# LED_Weather_Display.net
KiCad netlist of a schematic drawn in EAGLE
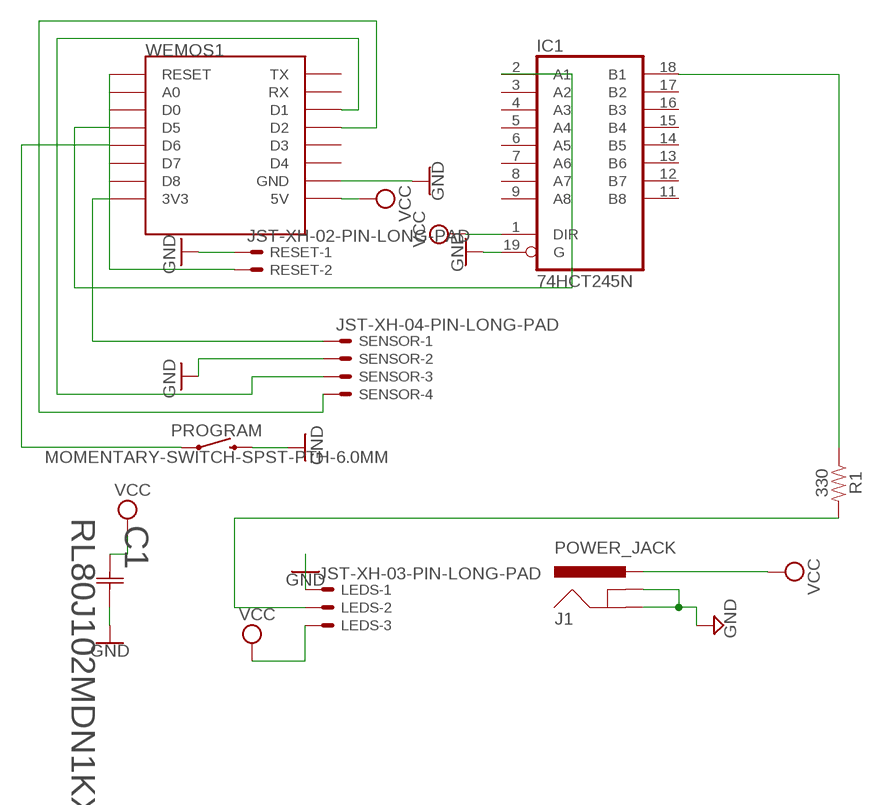
[diagram p0: schematic, sheet 1]

(export (version "E")
  (design (tool "Eeschema 10.0.6"))
  (components
    (comp (ref "C1")
      (value "RL80J102MDN1KX")
      (footprint "eagle-import:RL8")
      (libsource (lib "eagle-import") (part "RL80J102MDN1KX"))
    )
    (comp (ref "IC1")
      (value "74HCT245N")
      (footprint "eagle-import:DIL20")
      (libsource (lib "eagle-import") (part "74245NHCT"))
    )
    (comp (ref "J1")
      (value "POWER_JACK")
      (footprint "eagle-import:POWER_JACK_PTH")
      (libsource (lib "eagle-import") (part "POWER_JACK"))
    )
    (comp (ref "LEDS")
      (value "JST-XH-03-PIN-LONG-PAD")
      (footprint "eagle-import:JST-XH-03-PACKAGE-LONG-PAD")
      (libsource (lib "eagle-import") (part "JST-XH-03-PIN-LONG-PAD"))
    )
    (comp (ref "PROGRAM")
      (value "MOMENTARY-SWITCH-SPST-PTH-6.0MM")
      (footprint "eagle-import:TACTILE_SWITCH_PTH_6.0MM")
      (libsource (lib "eagle-import") (part "MOMENTARY-SWITCH-SPST-PTH-6.0MM"))
    )
    (comp (ref "R1")
      (value "330")
      (footprint "eagle-import:AXIAL-0.3")
      (libsource (lib "eagle-import") (part "330OHM-HORIZ-1/10W-5%"))
    )
    (comp (ref "RESET")
      (value "JST-XH-02-PIN-LONG-PAD")
      (footprint "eagle-import:JST-XH-02-PACKAGE-LONG-PAD")
      (libsource (lib "eagle-import") (part "JST-XH-02-PIN-LONG-PAD"))
    )
    (comp (ref "SENSOR")
      (value "JST-XH-04-PIN-LONG-PAD")
      (footprint "eagle-import:JST-XH-04-PACKAGE-LONG-PAD")
      (libsource (lib "eagle-import") (part "JST-XH-04-PIN-LONG-PAD"))
    )
    (comp (ref "WEMOS1")
      (value "WEMOS-D1-MINI")
      (footprint "eagle-import:WEMOS-D1-MINI")
      (libsource (lib "eagle-import") (part "WEMOS-D1-MINI"))
    )
  )
  (nets
    (net (code "1") (name "GND") (class "Default")
      (node (ref "C1") (pin "2") (pinfunction "22_2") (pintype "passive"))
      (node (ref "IC1") (pin "19") (pinfunction "G_19") (pintype "input"))
      (node (ref "J1") (pin "GND") (pinfunction "GND_GND") (pintype "bidirectional"))
      (node (ref "J1") (pin "GNDBREAK") (pinfunction "GNDBREAK_GNDBREAK") (pintype "bidirectional"))
      (node (ref "LEDS") (pin "1") (pinfunction "S_1") (pintype "passive"))
      (node (ref "PROGRAM") (pin "3") (pinfunction "2_3") (pintype "passive"))
      (node (ref "RESET") (pin "1") (pinfunction "S_1") (pintype "passive"))
      (node (ref "SENSOR") (pin "2") (pinfunction "S_2") (pintype "passive"))
      (node (ref "WEMOS1") (pin "GND") (pinfunction "GND_GND") (pintype "bidirectional"))
    )
    (net (code "2") (name "Net-(IC1A-A1)") (class "Default")
      (node (ref "IC1") (pin "2") (pinfunction "A1_2") (pintype "bidirectional"))
      (node (ref "WEMOS1") (pin "D5") (pinfunction "D5_D5") (pintype "bidirectional"))
    )
    (net (code "3") (name "Net-(IC1A-B1)") (class "Default")
      (node (ref "IC1") (pin "18") (pinfunction "B1_18") (pintype "bidirectional"))
      (node (ref "R1") (pin "P$1") (pinfunction "1_P$1") (pintype "passive"))
    )
    (net (code "4") (name "Net-(LEDSB-S)") (class "Default")
      (node (ref "LEDS") (pin "2") (pinfunction "S_2") (pintype "passive"))
      (node (ref "R1") (pin "P$2") (pinfunction "2_P$2") (pintype "passive"))
    )
    (net (code "5") (name "Net-(PROGRAM-Pad1)") (class "Default")
      (node (ref "PROGRAM") (pin "1") (pinfunction "1_1") (pintype "passive"))
      (node (ref "WEMOS1") (pin "D6") (pinfunction "D6_D6") (pintype "bidirectional"))
    )
    (net (code "6") (name "Net-(RESETB-S)") (class "Default")
      (node (ref "RESET") (pin "2") (pinfunction "S_2") (pintype "passive"))
      (node (ref "WEMOS1") (pin "RESET") (pinfunction "RESET_RESET") (pintype "bidirectional"))
    )
    (net (code "7") (name "Net-(SENSORA-S)") (class "Default")
      (node (ref "SENSOR") (pin "1") (pinfunction "S_1") (pintype "passive"))
      (node (ref "WEMOS1") (pin "3V3") (pinfunction "3V3_3V3") (pintype "bidirectional"))
    )
    (net (code "8") (name "Net-(SENSORC-S)") (class "Default")
      (node (ref "SENSOR") (pin "3") (pinfunction "S_3") (pintype "passive"))
      (node (ref "WEMOS1") (pin "D1") (pinfunction "D1_D1") (pintype "bidirectional"))
    )
    (net (code "9") (name "Net-(SENSORD-S)") (class "Default")
      (node (ref "SENSOR") (pin "4") (pinfunction "S_4") (pintype "passive"))
      (node (ref "WEMOS1") (pin "D2") (pinfunction "D2_D2") (pintype "bidirectional"))
    )
    (net (code "10") (name "VCC") (class "Default")
      (node (ref "C1") (pin "1") (pinfunction "11_1") (pintype "passive"))
      (node (ref "IC1") (pin "1") (pinfunction "DIR_1") (pintype "input"))
      (node (ref "J1") (pin "PWR") (pinfunction "PWR_PWR") (pintype "bidirectional"))
      (node (ref "LEDS") (pin "3") (pinfunction "S_3") (pintype "passive"))
      (node (ref "WEMOS1") (pin "5V") (pinfunction "5V_5V") (pintype "bidirectional"))
    )
    (net (code "11") (name "unconnected-(IC1A-A2-Pad3)") (class "Default")
      (node (ref "IC1") (pin "3") (pinfunction "A2_3") (pintype "bidirectional"))
    )
    (net (code "12") (name "unconnected-(IC1A-A3-Pad4)") (class "Default")
      (node (ref "IC1") (pin "4") (pinfunction "A3_4") (pintype "bidirectional"))
    )
    (net (code "13") (name "unconnected-(IC1A-A4-Pad5)") (class "Default")
      (node (ref "IC1") (pin "5") (pinfunction "A4_5") (pintype "bidirectional"))
    )
    (net (code "14") (name "unconnected-(IC1A-A5-Pad6)") (class "Default")
      (node (ref "IC1") (pin "6") (pinfunction "A5_6") (pintype "bidirectional"))
    )
    (net (code "15") (name "unconnected-(IC1A-A6-Pad7)") (class "Default")
      (node (ref "IC1") (pin "7") (pinfunction "A6_7") (pintype "bidirectional"))
    )
    (net (code "16") (name "unconnected-(IC1A-A7-Pad8)") (class "Default")
      (node (ref "IC1") (pin "8") (pinfunction "A7_8") (pintype "bidirectional"))
    )
    (net (code "17") (name "unconnected-(IC1A-A8-Pad9)") (class "Default")
      (node (ref "IC1") (pin "9") (pinfunction "A8_9") (pintype "bidirectional"))
    )
    (net (code "18") (name "unconnected-(IC1A-B2-Pad17)") (class "Default")
      (node (ref "IC1") (pin "17") (pinfunction "B2_17") (pintype "bidirectional"))
    )
    (net (code "19") (name "unconnected-(IC1A-B3-Pad16)") (class "Default")
      (node (ref "IC1") (pin "16") (pinfunction "B3_16") (pintype "bidirectional"))
    )
    (net (code "20") (name "unconnected-(IC1A-B4-Pad15)") (class "Default")
      (node (ref "IC1") (pin "15") (pinfunction "B4_15") (pintype "bidirectional"))
    )
    (net (code "21") (name "unconnected-(IC1A-B5-Pad14)") (class "Default")
      (node (ref "IC1") (pin "14") (pinfunction "B5_14") (pintype "bidirectional"))
    )
    (net (code "22") (name "unconnected-(IC1A-B6-Pad13)") (class "Default")
      (node (ref "IC1") (pin "13") (pinfunction "B6_13") (pintype "bidirectional"))
    )
    (net (code "23") (name "unconnected-(IC1A-B7-Pad12)") (class "Default")
      (node (ref "IC1") (pin "12") (pinfunction "B7_12") (pintype "bidirectional"))
    )
    (net (code "24") (name "unconnected-(IC1A-B8-Pad11)") (class "Default")
      (node (ref "IC1") (pin "11") (pinfunction "B8_11") (pintype "bidirectional"))
    )
    (net (code "25") (name "unconnected-(WEMOS1-PadA0)") (class "Default")
      (node (ref "WEMOS1") (pin "A0") (pinfunction "A0_A0") (pintype "bidirectional"))
    )
    (net (code "26") (name "unconnected-(WEMOS1-PadD0)") (class "Default")
      (node (ref "WEMOS1") (pin "D0") (pinfunction "D0_D0") (pintype "bidirectional"))
    )
    (net (code "27") (name "unconnected-(WEMOS1-PadD3)") (class "Default")
      (node (ref "WEMOS1") (pin "D3") (pinfunction "D3_D3") (pintype "bidirectional"))
    )
    (net (code "28") (name "unconnected-(WEMOS1-PadD4)") (class "Default")
      (node (ref "WEMOS1") (pin "D4") (pinfunction "D4_D4") (pintype "bidirectional"))
    )
    (net (code "29") (name "unconnected-(WEMOS1-PadD7)") (class "Default")
      (node (ref "WEMOS1") (pin "D7") (pinfunction "D7_D7") (pintype "bidirectional"))
    )
    (net (code "30") (name "unconnected-(WEMOS1-PadD8)") (class "Default")
      (node (ref "WEMOS1") (pin "D8") (pinfunction "D8_D8") (pintype "bidirectional"))
    )
    (net (code "31") (name "unconnected-(WEMOS1-PadRX)") (class "Default")
      (node (ref "WEMOS1") (pin "RX") (pinfunction "RX_RX") (pintype "bidirectional"))
    )
    (net (code "32") (name "unconnected-(WEMOS1-PadTX)") (class "Default")
      (node (ref "WEMOS1") (pin "TX") (pinfunction "TX_TX") (pintype "bidirectional"))
    )
  )
)
